# FLIGHT-CONTROLLER-Final_VERSION-1.net
KiCad netlist of a schematic drawn in EasyEDA Pro
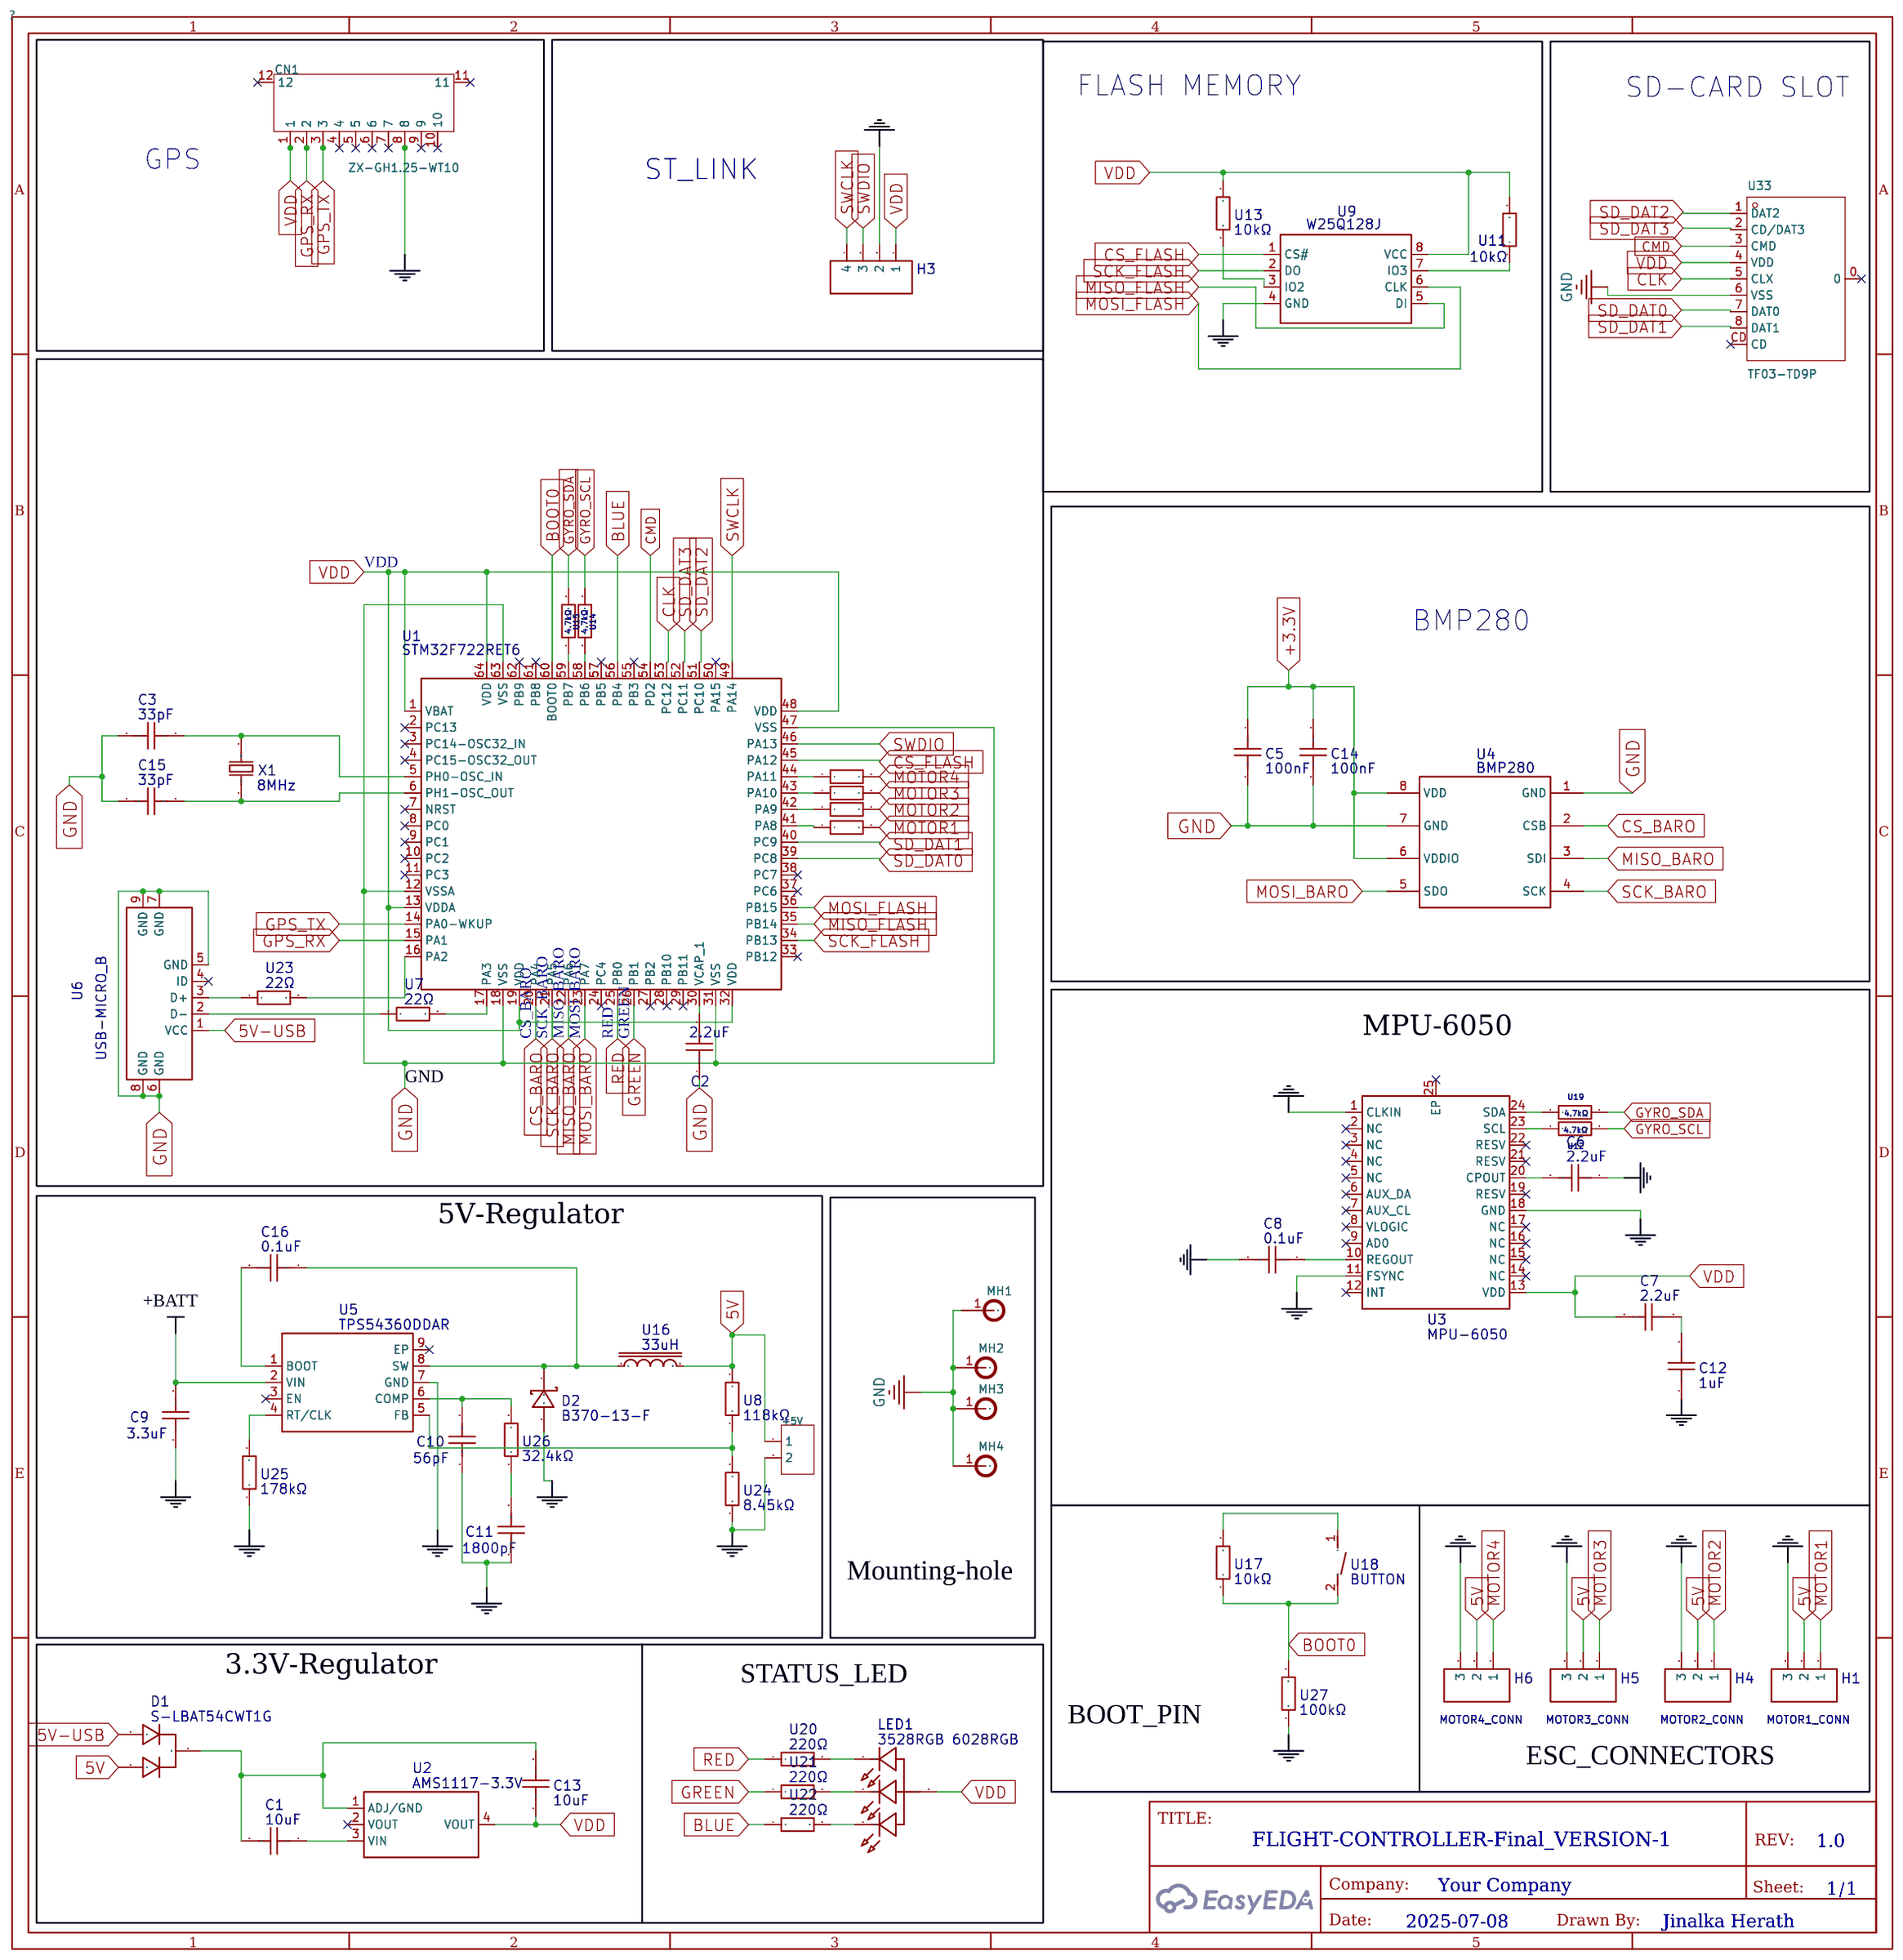
[diagram p0: schematic sheet]

(export (version "E")
  (design (tool "Eeschema 10.0.6"))
  (components
    (comp (ref "+5V")
      (value "~")
      (footprint "easyedapro:HDR-TH_2P-P2.54-V-F")
      (libsource (lib "easyedapro") (part "Header-Female-2.54_1x2"))
    )
    (comp (ref "C1")
      (value "10uF")
      (footprint "easyedapro:C0603")
      (fields
        (field (name "Manufacturer Part") "C1608CH2A560J080AA")
        (field (name "Manufacturer") "TDK")
        (field (name "Contributor") "lcsc")
      )
      (libsource (lib "easyedapro") (part "10uF"))
    )
    (comp (ref "C2")
      (value "2.2uF")
      (footprint "easyedapro:CAP-SMD_L3.2-W2.5-1")
      (fields
        (field (name "Manufacturer Part") "25MU225MB23225")
        (field (name "Manufacturer") "rubycon(红宝石)")
        (field (name "Contributor") "lcsc")
      )
      (libsource (lib "easyedapro") (part "2.2uF"))
    )
    (comp (ref "C3")
      (value "33pF")
      (footprint "easyedapro:C0603")
      (fields
        (field (name "Manufacturer Part") "C1608CH2A560J080AA")
        (field (name "Manufacturer") "TDK")
        (field (name "Contributor") "lcsc")
      )
      (libsource (lib "easyedapro") (part "33pF"))
    )
    (comp (ref "C5")
      (value "100nF")
      (footprint "easyedapro:C0603")
      (fields
        (field (name "Manufacturer Part") "C1608CH2A560J080AA")
        (field (name "Manufacturer") "TDK")
        (field (name "Contributor") "lcsc")
      )
      (libsource (lib "easyedapro") (part "100nF"))
    )
    (comp (ref "C6")
      (value "2.2uF")
      (footprint "easyedapro:CAP-SMD_L3.2-W2.5-1")
      (fields
        (field (name "Manufacturer Part") "25MU225MB23225")
        (field (name "Manufacturer") "rubycon(红宝石)")
        (field (name "Contributor") "lcsc")
      )
      (libsource (lib "easyedapro") (part "2.2uF"))
    )
    (comp (ref "C7")
      (value "2.2uF")
      (footprint "easyedapro:CAP-SMD_L3.2-W2.5-1")
      (fields
        (field (name "Manufacturer Part") "25MU225MB23225")
        (field (name "Manufacturer") "rubycon(红宝石)")
        (field (name "Contributor") "lcsc")
      )
      (libsource (lib "easyedapro") (part "2.2uF"))
    )
    (comp (ref "C8")
      (value "0.1uF")
      (footprint "easyedapro:C0603")
      (fields
        (field (name "Manufacturer Part") "C1608CH2A560J080AA")
        (field (name "Manufacturer") "TDK")
        (field (name "Contributor") "lcsc")
      )
      (libsource (lib "easyedapro") (part "0.1uF"))
    )
    (comp (ref "C9")
      (value "3.3uF")
      (footprint "easyedapro:C0603")
      (fields
        (field (name "Manufacturer Part") "C1608CH2A560J080AA")
        (field (name "Manufacturer") "TDK")
        (field (name "Contributor") "lcsc")
      )
      (libsource (lib "easyedapro") (part "3.3uF"))
    )
    (comp (ref "C10")
      (value "56pF")
      (footprint "easyedapro:C0603")
      (fields
        (field (name "Manufacturer Part") "C1608CH2A560J080AA")
        (field (name "Manufacturer") "TDK")
        (field (name "Contributor") "lcsc")
      )
      (libsource (lib "easyedapro") (part "56pF"))
    )
    (comp (ref "C11")
      (value "1800pF")
      (footprint "easyedapro:C0603")
      (fields
        (field (name "Manufacturer Part") "C1608CH2A560J080AA")
        (field (name "Manufacturer") "TDK")
        (field (name "Contributor") "lcsc")
      )
      (libsource (lib "easyedapro") (part "1800pF"))
    )
    (comp (ref "C12")
      (value "1uF")
      (footprint "easyedapro:C0603")
      (fields
        (field (name "Manufacturer Part") "C1608CH2A560J080AA")
        (field (name "Manufacturer") "TDK")
        (field (name "Contributor") "lcsc")
      )
      (libsource (lib "easyedapro") (part "1uF"))
    )
    (comp (ref "C13")
      (value "10uF")
      (footprint "easyedapro:C0603")
      (fields
        (field (name "Manufacturer Part") "C1608CH2A560J080AA")
        (field (name "Manufacturer") "TDK")
        (field (name "Contributor") "lcsc")
      )
      (libsource (lib "easyedapro") (part "10uF"))
    )
    (comp (ref "C14")
      (value "100nF")
      (footprint "easyedapro:C0603")
      (fields
        (field (name "Manufacturer Part") "C1608CH2A560J080AA")
        (field (name "Manufacturer") "TDK")
        (field (name "Contributor") "lcsc")
      )
      (libsource (lib "easyedapro") (part "100nF"))
    )
    (comp (ref "C15")
      (value "33pF")
      (footprint "easyedapro:C0603")
      (fields
        (field (name "Manufacturer Part") "C1608CH2A560J080AA")
        (field (name "Manufacturer") "TDK")
        (field (name "Contributor") "lcsc")
      )
      (libsource (lib "easyedapro") (part "33pF"))
    )
    (comp (ref "C16")
      (value "0.1uF")
      (footprint "easyedapro:C0603")
      (fields
        (field (name "Manufacturer Part") "C1608CH2A560J080AA")
        (field (name "Manufacturer") "TDK")
        (field (name "Contributor") "lcsc")
      )
      (libsource (lib "easyedapro") (part "0.1uF"))
    )
    (comp (ref "CN1")
      (value "ZX-GH1.25-WT10")
      (footprint "easyedapro:CONN-SMD_ZX-GH1.25-WT10")
      (fields (field (name "Manufacturer") "Megastar(兆星)"))
      (libsource (lib "easyedapro") (part "ZX-GH1.25-WT10"))
    )
    (comp (ref "D1")
      (value "S-LBAT54CWT1G")
      (footprint "easyedapro:SC-70-3_L2.0-W1.3-P1.30-LS2.1-BR")
      (fields (field (name "Manufacturer") "LRC(乐山无线电)") (field (name "Contributor") "lcsc"))
      (libsource (lib "easyedapro") (part "S-LBAT54CWT1G"))
    )
    (comp (ref "D2")
      (value "B370-13-F")
      (footprint "easyedapro:SMC_L7.1-W6.2-LS8.1-RD")
      (fields (field (name "Manufacturer") "DIODES(美台)") (field (name "Contributor") "LCSC"))
      (libsource (lib "easyedapro") (part "B370-13-F"))
    )
    (comp (ref "H1")
      (value "MOTOR1_CONN")
      (footprint "easyedapro:HDR-F-2.54_1X3")
      (fields (field (name "Contributor") "LCEDA_Lib"))
      (libsource (lib "easyedapro") (part "MOTOR1_CONN"))
    )
    (comp (ref "H3")
      (value "ST_LINK")
      (footprint "easyedapro:HDR-F-2.54_1X4")
      (fields (field (name "Contributor") "LCEDA_Lib"))
      (libsource (lib "easyedapro") (part "ST_LINK"))
    )
    (comp (ref "H4")
      (value "MOTOR2_CONN")
      (footprint "easyedapro:HDR-F-2.54_1X3")
      (fields (field (name "Contributor") "LCEDA_Lib"))
      (libsource (lib "easyedapro") (part "MOTOR2_CONN"))
    )
    (comp (ref "H5")
      (value "MOTOR3_CONN")
      (footprint "easyedapro:HDR-F-2.54_1X3")
      (fields (field (name "Contributor") "LCEDA_Lib"))
      (libsource (lib "easyedapro") (part "MOTOR3_CONN"))
    )
    (comp (ref "H6")
      (value "MOTOR4_CONN")
      (footprint "easyedapro:HDR-F-2.54_1X3")
      (fields (field (name "Contributor") "LCEDA_Lib"))
      (libsource (lib "easyedapro") (part "MOTOR4_CONN"))
    )
    (comp (ref "LED1")
      (value "3528RGB 6028RGB")
      (footprint "easyedapro:LED-SMD_4P-L3.5-W2.8_3528RGB-6028RGB")
      (fields
        (field (name "Manufacturer Part") "3528反贴RGB 6028反贴RGB 缺口蓝色")
        (field (name "Contributor") "lcsc")
      )
      (libsource (lib "easyedapro") (part "3528RGB 6028RGB"))
    )
    (comp (ref "MH1")
      (value "~")
      (footprint "easyedapro:MH_7.5")
      (libsource (lib "easyedapro") (part "MH_7.5"))
    )
    (comp (ref "MH2")
      (value "~")
      (footprint "easyedapro:MH_7.5")
      (libsource (lib "easyedapro") (part "MH_7.5"))
    )
    (comp (ref "MH3")
      (value "~")
      (footprint "easyedapro:MH_7.5")
      (libsource (lib "easyedapro") (part "MH_7.5"))
    )
    (comp (ref "MH4")
      (value "~")
      (footprint "easyedapro:MH_7.5")
      (libsource (lib "easyedapro") (part "MH_7.5"))
    )
    (comp (ref "U1")
      (value "STM32F722RET6")
      (footprint "easyedapro:LQFP-64_L10.0-W10.0-P0.50-LS12.0-BL")
      (fields (field (name "Manufacturer") "ST(意法半导体)") (field (name "Contributor") "LCSC"))
      (libsource (lib "easyedapro") (part "STM32F722RET6"))
    )
    (comp (ref "U2")
      (value "AMS1117-3.3V")
      (footprint "easyedapro:SOT-223-4_L6.5-W3.5-P2.30-LS7.0-BR")
      (fields (field (name "Manufacturer") "WPMtek(维攀)") (field (name "Contributor") "LCSC"))
      (libsource (lib "easyedapro") (part "AMS1117-3.3V"))
    )
    (comp (ref "U3")
      (value "MPU-6050")
      (footprint "easyedapro:QFN-24_L4.0-W4.0-P0.50-BL-EP2.7")
      (fields (field (name "Manufacturer") "TDK InvenSense(应美盛)"))
      (libsource (lib "easyedapro") (part "MPU-6050_C24112"))
    )
    (comp (ref "U4")
      (value "BMP280")
      (footprint "easyedapro:LGA-8_L2.5-W2.0-P0.65_AMP6127")
      (fields (field (name "Manufacturer") "Bosch(博世)"))
      (libsource (lib "easyedapro") (part "BMP280"))
    )
    (comp (ref "U5")
      (value "TPS54360DDAR")
      (footprint "easyedapro:ESOP-8_L4.9-W3.9-P1.27-LS6.0-BL-EP")
      (fields
        (field (name "Manufacturer Part") "TPS54360DDAR(TOKMAS)")
        (field (name "Manufacturer") "Tokmas(托克马斯)")
        (field (name "Contributor") "lcsc")
      )
      (libsource (lib "easyedapro") (part "TPS54360DDAR(TOKMAS)"))
    )
    (comp (ref "U6")
      (value "USB-MICRO_B")
      (footprint "easyedapro:MICRO-USB-SMD_USB-MICRO_B")
      (fields (field (name "Contributor") "LCSC"))
      (libsource (lib "easyedapro") (part "USB-MICRO_B"))
    )
    (comp (ref "U7")
      (value "22Ω")
      (footprint "easyedapro:RES-TH_BD2.3-L3.7-P7.70-D0.9")
      (fields
        (field (name "Manufacturer Part") "MF1/8W-220Ω±1%-ST52")
        (field (name "Manufacturer") "VO(翔胜)")
        (field (name "Contributor") "lcsc")
      )
      (libsource (lib "easyedapro") (part "22Ω"))
    )
    (comp (ref "U8")
      (value "118kΩ")
      (footprint "easyedapro:RES-TH_BD2.3-L3.7-P7.70-D0.9")
      (fields
        (field (name "Manufacturer Part") "MF1/8W-220Ω±1%-ST52")
        (field (name "Manufacturer") "VO(翔胜)")
        (field (name "Contributor") "lcsc")
      )
      (libsource (lib "easyedapro") (part "118kΩ"))
    )
    (comp (ref "U9")
      (value "W25Q128J")
      (footprint "easyedapro:SOIC-8_L5.3-W5.3-P1.27-LS8.0-BL")
      (fields (field (name "Manufacturer Part") "W25Q128JVSIQ") (field (name "Manufacturer") "WINBOND(华邦)"))
      (libsource (lib "easyedapro") (part "W25Q128JVSIQTR"))
    )
    (comp (ref "U11")
      (value "10kΩ")
      (footprint "easyedapro:RES-TH_BD2.3-L3.7-P7.70-D0.9")
      (fields
        (field (name "Manufacturer Part") "MF1/8W-220Ω±1%-ST52")
        (field (name "Manufacturer") "VO(翔胜)")
        (field (name "Contributor") "lcsc")
      )
      (libsource (lib "easyedapro") (part "10kΩ"))
    )
    (comp (ref "U12")
      (value "4.7kΩ")
      (footprint "easyedapro:RES-TH_BD2.3-L3.7-P7.70-D0.9")
      (fields
        (field (name "Manufacturer Part") "MF1/8W-220Ω±1%-ST52")
        (field (name "Manufacturer") "VO(翔胜)")
        (field (name "Contributor") "lcsc")
      )
      (libsource (lib "easyedapro") (part "4.7kΩ"))
    )
    (comp (ref "U13")
      (value "10kΩ")
      (footprint "easyedapro:RES-TH_BD2.3-L3.7-P7.70-D0.9")
      (fields
        (field (name "Manufacturer Part") "MF1/8W-220Ω±1%-ST52")
        (field (name "Manufacturer") "VO(翔胜)")
        (field (name "Contributor") "lcsc")
      )
      (libsource (lib "easyedapro") (part "10kΩ"))
    )
    (comp (ref "U14")
      (value "4.7kΩ")
      (footprint "easyedapro:RES-TH_BD2.3-L3.7-P7.70-D0.9")
      (fields
        (field (name "Manufacturer Part") "MF1/8W-220Ω±1%-ST52")
        (field (name "Manufacturer") "VO(翔胜)")
        (field (name "Contributor") "lcsc")
      )
      (libsource (lib "") (part "4.7kΩ_1"))
    )
    (comp (ref "U15")
      (value "4.7kΩ")
      (footprint "easyedapro:RES-TH_BD2.3-L3.7-P7.70-D0.9")
      (fields
        (field (name "Manufacturer Part") "MF1/8W-220Ω±1%-ST52")
        (field (name "Manufacturer") "VO(翔胜)")
        (field (name "Contributor") "lcsc")
      )
      (libsource (lib "") (part "4.7kΩ_1"))
    )
    (comp (ref "U16")
      (value "33uH")
      (footprint "easyedapro:IND-SMD_L8.5-W8.0_SMS0850")
      (fields
        (field (name "Manufacturer Part") "SMS0850-330MT")
        (field (name "Manufacturer") "LanTu Micro(蓝图微电)")
        (field (name "Contributor") "lcsc")
      )
      (libsource (lib "easyedapro") (part "33uH"))
    )
    (comp (ref "U17")
      (value "10kΩ")
      (footprint "easyedapro:RES-TH_BD2.3-L3.7-P7.70-D0.9")
      (fields
        (field (name "Manufacturer Part") "MF1/8W-220Ω±1%-ST52")
        (field (name "Manufacturer") "VO(翔胜)")
        (field (name "Contributor") "lcsc")
      )
      (libsource (lib "easyedapro") (part "10kΩ"))
    )
    (comp (ref "U18")
      (value "BUTTON")
      (footprint "easyedapro:KEY-SMD_L6.0-W6.0-LS6.6")
      (fields (field (name "Contributor") "lcsc"))
      (libsource (lib "easyedapro") (part "BUTTON"))
    )
    (comp (ref "U19")
      (value "4.7kΩ")
      (footprint "easyedapro:RES-TH_BD2.3-L3.7-P7.70-D0.9")
      (fields
        (field (name "Manufacturer Part") "MF1/8W-220Ω±1%-ST52")
        (field (name "Manufacturer") "VO(翔胜)")
        (field (name "Contributor") "lcsc")
      )
      (libsource (lib "easyedapro") (part "4.7kΩ"))
    )
    (comp (ref "U20")
      (value "220Ω")
      (footprint "easyedapro:RES-TH_BD2.3-L3.7-P7.70-D0.9")
      (fields
        (field (name "Manufacturer Part") "MF1/8W-220Ω±1%-ST52")
        (field (name "Manufacturer") "VO(翔胜)")
        (field (name "Contributor") "lcsc")
      )
      (libsource (lib "easyedapro") (part "220Ω"))
    )
    (comp (ref "U21")
      (value "220Ω")
      (footprint "easyedapro:RES-TH_BD2.3-L3.7-P7.70-D0.9")
      (fields
        (field (name "Manufacturer Part") "MF1/8W-220Ω±1%-ST52")
        (field (name "Manufacturer") "VO(翔胜)")
        (field (name "Contributor") "lcsc")
      )
      (libsource (lib "easyedapro") (part "220Ω"))
    )
    (comp (ref "U22")
      (value "220Ω")
      (footprint "easyedapro:RES-TH_BD2.3-L3.7-P7.70-D0.9")
      (fields
        (field (name "Manufacturer Part") "MF1/8W-220Ω±1%-ST52")
        (field (name "Manufacturer") "VO(翔胜)")
        (field (name "Contributor") "lcsc")
      )
      (libsource (lib "easyedapro") (part "220Ω"))
    )
    (comp (ref "U23")
      (value "22Ω")
      (footprint "easyedapro:RES-TH_BD2.3-L3.7-P7.70-D0.9")
      (fields
        (field (name "Manufacturer Part") "MF1/8W-220Ω±1%-ST52")
        (field (name "Manufacturer") "VO(翔胜)")
        (field (name "Contributor") "lcsc")
      )
      (libsource (lib "easyedapro") (part "22Ω"))
    )
    (comp (ref "U24")
      (value "8.45kΩ")
      (footprint "easyedapro:RES-TH_BD2.3-L3.7-P7.70-D0.9")
      (fields
        (field (name "Manufacturer Part") "MF1/8W-220Ω±1%-ST52")
        (field (name "Manufacturer") "VO(翔胜)")
        (field (name "Contributor") "lcsc")
      )
      (libsource (lib "easyedapro") (part "8.45kΩ"))
    )
    (comp (ref "U25")
      (value "178kΩ")
      (footprint "easyedapro:RES-TH_BD2.3-L3.7-P7.70-D0.9")
      (fields
        (field (name "Manufacturer Part") "MF1/8W-220Ω±1%-ST52")
        (field (name "Manufacturer") "VO(翔胜)")
        (field (name "Contributor") "lcsc")
      )
      (libsource (lib "easyedapro") (part "178kΩ"))
    )
    (comp (ref "U26")
      (value "32.4kΩ")
      (footprint "easyedapro:RES-TH_BD2.3-L3.7-P7.70-D0.9")
      (fields
        (field (name "Manufacturer Part") "MF1/8W-220Ω±1%-ST52")
        (field (name "Manufacturer") "VO(翔胜)")
        (field (name "Contributor") "lcsc")
      )
      (libsource (lib "easyedapro") (part "32.4kΩ"))
    )
    (comp (ref "U27")
      (value "100kΩ")
      (footprint "easyedapro:RES-TH_BD2.3-L3.7-P7.70-D0.9")
      (fields
        (field (name "Manufacturer Part") "MF1/8W-220Ω±1%-ST52")
        (field (name "Manufacturer") "VO(翔胜)")
        (field (name "Contributor") "lcsc")
      )
      (libsource (lib "easyedapro") (part "100kΩ"))
    )
    (comp (ref "U28")
      (value "100Ω")
      (footprint "easyedapro:RES-TH_BD2.3-L3.7-P7.70-D0.9")
      (fields
        (field (name "Manufacturer Part") "MF1/8W-220Ω±1%-ST52")
        (field (name "Manufacturer") "VO(翔胜)")
        (field (name "Contributor") "lcsc")
      )
      (libsource (lib "easyedapro") (part "100Ω"))
    )
    (comp (ref "U29")
      (value "100Ω")
      (footprint "easyedapro:RES-TH_BD2.3-L3.7-P7.70-D0.9")
      (fields
        (field (name "Manufacturer Part") "MF1/8W-220Ω±1%-ST52")
        (field (name "Manufacturer") "VO(翔胜)")
        (field (name "Contributor") "lcsc")
      )
      (libsource (lib "easyedapro") (part "100Ω"))
    )
    (comp (ref "U30")
      (value "100Ω")
      (footprint "easyedapro:RES-TH_BD2.3-L3.7-P7.70-D0.9")
      (fields
        (field (name "Manufacturer Part") "MF1/8W-220Ω±1%-ST52")
        (field (name "Manufacturer") "VO(翔胜)")
        (field (name "Contributor") "lcsc")
      )
      (libsource (lib "easyedapro") (part "100Ω"))
    )
    (comp (ref "U33")
      (value "TF03-TD9P")
      (footprint "easyedapro:CONN-SMD_TF-001A-P")
      (fields (field (name "Manufacturer") "BXCONN(宝讯)"))
      (libsource (lib "easyedapro") (part "TF03-TD9P"))
    )
    (comp (ref "U34")
      (value "100Ω")
      (footprint "easyedapro:RES-TH_BD2.3-L3.7-P7.70-D0.9")
      (fields
        (field (name "Manufacturer Part") "MF1/8W-220Ω±1%-ST52")
        (field (name "Manufacturer") "VO(翔胜)")
        (field (name "Contributor") "lcsc")
      )
      (libsource (lib "easyedapro") (part "100Ω"))
    )
    (comp (ref "X1")
      (value "8MHz")
      (footprint "easyedapro:CRYSTAL-SMD_L3.2-W2.5_3225-8MHZ")
      (fields
        (field (name "Manufacturer Part") "X22EL89COI-111YLC-8M")
        (field (name "Manufacturer") "YXC(扬兴晶振)")
        (field (name "Contributor") "lcsc")
      )
      (libsource (lib "easyedapro") (part "8MHz"))
    )
  )
  (nets
    (net (code "1") (name "+3.3V") (class "Default")
      (node (ref "C14") (pin "1") (pinfunction "1_1") (pintype "unspecified"))
      (node (ref "C5") (pin "1") (pinfunction "1_1") (pintype "unspecified"))
      (node (ref "U4") (pin "6") (pinfunction "VDDIO_6") (pintype "unspecified"))
      (node (ref "U4") (pin "8") (pinfunction "VDD_8") (pintype "unspecified"))
    )
    (net (code "2") (name "+BATT") (class "Default")
      (node (ref "C9") (pin "2") (pinfunction "2_2") (pintype "unspecified"))
      (node (ref "U5") (pin "2") (pinfunction "VIN_2") (pintype "unspecified"))
    )
    (net (code "3") (name "5V") (class "Default")
      (node (ref "+5V") (pin "1") (pinfunction "1_1") (pintype "input"))
      (node (ref "D1") (pin "2") (pinfunction "2_2") (pintype "unspecified"))
      (node (ref "H1") (pin "2") (pinfunction "2_2") (pintype "input"))
      (node (ref "H4") (pin "2") (pinfunction "2_2") (pintype "input"))
      (node (ref "H5") (pin "2") (pinfunction "2_2") (pintype "input"))
      (node (ref "H6") (pin "2") (pinfunction "2_2") (pintype "input"))
      (node (ref "U16") (pin "2") (pinfunction "2_2") (pintype "unspecified"))
      (node (ref "U8") (pin "2") (pinfunction "2_2") (pintype "unspecified"))
    )
    (net (code "4") (name "5V-USB") (class "Default")
      (node (ref "D1") (pin "1") (pinfunction "1_1") (pintype "unspecified"))
      (node (ref "U6") (pin "1") (pinfunction "VCC_1") (pintype "unspecified"))
    )
    (net (code "5") (name "BLUE") (class "Default")
      (node (ref "U1") (pin "56") (pinfunction "PB4_56") (pintype "unspecified"))
      (node (ref "U22") (pin "1") (pinfunction "1_1") (pintype "unspecified"))
    )
    (net (code "6") (name "BOOT0") (class "Default")
      (node (ref "U1") (pin "60") (pinfunction "BOOT0_60") (pintype "unspecified"))
      (node (ref "U17") (pin "1") (pinfunction "1_1") (pintype "unspecified"))
      (node (ref "U18") (pin "2") (pinfunction "B_2") (pintype "unspecified"))
      (node (ref "U27") (pin "2") (pinfunction "2_2") (pintype "unspecified"))
    )
    (net (code "7") (name "CLK") (class "Default")
      (node (ref "U1") (pin "53") (pinfunction "PC12_53") (pintype "unspecified"))
      (node (ref "U33") (pin "5") (pinfunction "CLX_5") (pintype "unspecified"))
    )
    (net (code "8") (name "CMD") (class "Default")
      (node (ref "U1") (pin "54") (pinfunction "PD2_54") (pintype "unspecified"))
      (node (ref "U33") (pin "3") (pinfunction "CMD_3") (pintype "unspecified"))
    )
    (net (code "9") (name "CS_BARO") (class "Default")
      (node (ref "U1") (pin "20") (pinfunction "PA4_20") (pintype "unspecified"))
      (node (ref "U4") (pin "2") (pinfunction "CSB_2") (pintype "unspecified"))
    )
    (net (code "10") (name "CS_FLASH") (class "Default")
      (node (ref "U1") (pin "45") (pinfunction "PA12_45") (pintype "unspecified"))
      (node (ref "U9") (pin "1") (pinfunction "CS#_1") (pintype "unspecified"))
    )
    (net (code "11") (name "GND") (class "Default")
      (node (ref "+5V") (pin "2") (pinfunction "2_2") (pintype "input"))
      (node (ref "C10") (pin "1") (pinfunction "1_1") (pintype "unspecified"))
      (node (ref "C11") (pin "1") (pinfunction "1_1") (pintype "unspecified"))
      (node (ref "C12") (pin "2") (pinfunction "2_2") (pintype "unspecified"))
      (node (ref "C14") (pin "2") (pinfunction "2_2") (pintype "unspecified"))
      (node (ref "C15") (pin "1") (pinfunction "1_1") (pintype "unspecified"))
      (node (ref "C2") (pin "1") (pinfunction "1_1") (pintype "unspecified"))
      (node (ref "C3") (pin "1") (pinfunction "1_1") (pintype "unspecified"))
      (node (ref "C5") (pin "2") (pinfunction "2_2") (pintype "unspecified"))
      (node (ref "C6") (pin "1") (pinfunction "1_1") (pintype "unspecified"))
      (node (ref "C8") (pin "2") (pinfunction "2_2") (pintype "unspecified"))
      (node (ref "C9") (pin "1") (pinfunction "1_1") (pintype "unspecified"))
      (node (ref "CN1") (pin "8") (pinfunction "8_8") (pintype "unspecified"))
      (node (ref "D2") (pin "2") (pinfunction "A_2") (pintype "unspecified"))
      (node (ref "H1") (pin "3") (pinfunction "3_3") (pintype "input"))
      (node (ref "H3") (pin "2") (pinfunction "2_2") (pintype "unspecified"))
      (node (ref "H4") (pin "3") (pinfunction "3_3") (pintype "input"))
      (node (ref "H5") (pin "3") (pinfunction "3_3") (pintype "input"))
      (node (ref "H6") (pin "3") (pinfunction "3_3") (pintype "input"))
      (node (ref "MH1") (pin "1") (pinfunction "1_1") (pintype "input"))
      (node (ref "MH2") (pin "1") (pinfunction "1_1") (pintype "input"))
      (node (ref "MH3") (pin "1") (pinfunction "1_1") (pintype "input"))
      (node (ref "MH4") (pin "1") (pinfunction "1_1") (pintype "input"))
      (node (ref "U1") (pin "12") (pinfunction "VSSA_12") (pintype "unspecified"))
      (node (ref "U1") (pin "18") (pinfunction "VSS_18") (pintype "unspecified"))
      (node (ref "U1") (pin "31") (pinfunction "VSS_31") (pintype "unspecified"))
      (node (ref "U1") (pin "47") (pinfunction "VSS_47") (pintype "unspecified"))
      (node (ref "U1") (pin "63") (pinfunction "VSS_63") (pintype "unspecified"))
      (node (ref "U24") (pin "1") (pinfunction "1_1") (pintype "unspecified"))
      (node (ref "U25") (pin "1") (pinfunction "1_1") (pintype "unspecified"))
      (node (ref "U27") (pin "1") (pinfunction "1_1") (pintype "unspecified"))
      (node (ref "U3") (pin "1") (pinfunction "CLKIN_1") (pintype "unspecified"))
      (node (ref "U3") (pin "11") (pinfunction "FSYNC_11") (pintype "unspecified"))
      (node (ref "U3") (pin "18") (pinfunction "GND_18") (pintype "unspecified"))
      (node (ref "U33") (pin "6") (pinfunction "VSS_6") (pintype "unspecified"))
      (node (ref "U4") (pin "1") (pinfunction "GND_1") (pintype "unspecified"))
      (node (ref "U4") (pin "7") (pinfunction "GND_7") (pintype "unspecified"))
      (node (ref "U5") (pin "7") (pinfunction "GND_7") (pintype "unspecified"))
      (node (ref "U6") (pin "5") (pinfunction "GND_5") (pintype "unspecified"))
      (node (ref "U6") (pin "6") (pinfunction "GND_6") (pintype "unspecified"))
      (node (ref "U6") (pin "7") (pinfunction "GND_7") (pintype "unspecified"))
      (node (ref "U6") (pin "8") (pinfunction "GND_8") (pintype "unspecified"))
      (node (ref "U6") (pin "9") (pinfunction "GND_9") (pintype "unspecified"))
      (node (ref "U9") (pin "4") (pinfunction "GND_4") (pintype "unspecified"))
    )
    (net (code "12") (name "GPS_RX") (class "Default")
      (node (ref "CN1") (pin "2") (pinfunction "2_2") (pintype "unspecified"))
      (node (ref "U1") (pin "15") (pinfunction "PA1_15") (pintype "unspecified"))
    )
    (net (code "13") (name "GPS_TX") (class "Default")
      (node (ref "CN1") (pin "3") (pinfunction "3_3") (pintype "unspecified"))
      (node (ref "U1") (pin "14") (pinfunction "PA0-WKUP_14") (pintype "unspecified"))
    )
    (net (code "14") (name "GREEN") (class "Default")
      (node (ref "U1") (pin "26") (pinfunction "PB1_26") (pintype "unspecified"))
      (node (ref "U21") (pin "1") (pinfunction "1_1") (pintype "unspecified"))
    )
    (net (code "15") (name "GYRO_SCL") (class "Default")
      (node (ref "U12") (pin "2") (pinfunction "2_2") (pintype "unspecified"))
      (node (ref "U14") (pin "2") (pinfunction "2_2") (pintype "unspecified"))
    )
    (net (code "16") (name "GYRO_SDA") (class "Default")
      (node (ref "U15") (pin "2") (pinfunction "2_2") (pintype "unspecified"))
      (node (ref "U19") (pin "2") (pinfunction "2_2") (pintype "unspecified"))
    )
    (net (code "17") (name "MISO_BARO") (class "Default")
      (node (ref "U1") (pin "22") (pinfunction "PA6_22") (pintype "unspecified"))
      (node (ref "U4") (pin "3") (pinfunction "SDI_3") (pintype "unspecified"))
    )
    (net (code "18") (name "MISO_FLASH") (class "Default")
      (node (ref "U1") (pin "35") (pinfunction "PB14_35") (pintype "unspecified"))
      (node (ref "U9") (pin "5") (pinfunction "DI_5") (pintype "unspecified"))
    )
    (net (code "19") (name "MOSI_BARO") (class "Default")
      (node (ref "U1") (pin "23") (pinfunction "PA7_23") (pintype "unspecified"))
      (node (ref "U4") (pin "5") (pinfunction "SDO_5") (pintype "unspecified"))
    )
    (net (code "20") (name "MOSI_FLASH") (class "Default")
      (node (ref "U1") (pin "36") (pinfunction "PB15_36") (pintype "unspecified"))
      (node (ref "U9") (pin "6") (pinfunction "CLK_6") (pintype "unspecified"))
    )
    (net (code "21") (name "MOTOR1") (class "Default")
      (node (ref "H1") (pin "1") (pinfunction "1_1") (pintype "input"))
      (node (ref "U34") (pin "2") (pinfunction "2_2") (pintype "unspecified"))
    )
    (net (code "22") (name "MOTOR2") (class "Default")
      (node (ref "H4") (pin "1") (pinfunction "1_1") (pintype "input"))
      (node (ref "U29") (pin "2") (pinfunction "2_2") (pintype "unspecified"))
    )
    (net (code "23") (name "MOTOR3") (class "Default")
      (node (ref "H5") (pin "1") (pinfunction "1_1") (pintype "input"))
      (node (ref "U28") (pin "2") (pinfunction "2_2") (pintype "unspecified"))
    )
    (net (code "24") (name "MOTOR4") (class "Default")
      (node (ref "H6") (pin "1") (pinfunction "1_1") (pintype "input"))
      (node (ref "U30") (pin "2") (pinfunction "2_2") (pintype "unspecified"))
    )
    (net (code "25") (name "Net-(C11-Pad2)") (class "Default")
      (node (ref "C11") (pin "2") (pinfunction "2_2") (pintype "unspecified"))
      (node (ref "U26") (pin "1") (pinfunction "1_1") (pintype "unspecified"))
    )
    (net (code "26") (name "Net-(C12-Pad1)") (class "Default")
      (node (ref "C12") (pin "1") (pinfunction "1_1") (pintype "unspecified"))
      (node (ref "C7") (pin "1") (pinfunction "1_1") (pintype "unspecified"))
    )
    (net (code "27") (name "Net-(D2-C)") (class "Default")
      (node (ref "C16") (pin "1") (pinfunction "1_1") (pintype "unspecified"))
      (node (ref "D2") (pin "1") (pinfunction "C_1") (pintype "unspecified"))
      (node (ref "U16") (pin "1") (pinfunction "1_1") (pintype "unspecified"))
      (node (ref "U5") (pin "8") (pinfunction "SW_8") (pintype "unspecified"))
    )
    (net (code "28") (name "Net-(LED1-B)") (class "Default")
      (node (ref "LED1") (pin "1") (pinfunction "B_1") (pintype "unspecified"))
      (node (ref "U21") (pin "2") (pinfunction "2_2") (pintype "unspecified"))
    )
    (net (code "29") (name "Net-(LED1-G)") (class "Default")
      (node (ref "LED1") (pin "4") (pinfunction "G_4") (pintype "unspecified"))
      (node (ref "U22") (pin "2") (pinfunction "2_2") (pintype "unspecified"))
    )
    (net (code "30") (name "Net-(LED1-R)") (class "Default")
      (node (ref "LED1") (pin "2") (pinfunction "R_2") (pintype "unspecified"))
      (node (ref "U20") (pin "2") (pinfunction "2_2") (pintype "unspecified"))
    )
    (net (code "31") (name "Net-(U1-PA2)") (class "Default")
      (node (ref "U1") (pin "16") (pinfunction "PA2_16") (pintype "unspecified"))
      (node (ref "U23") (pin "2") (pinfunction "2_2") (pintype "unspecified"))
    )
    (net (code "32") (name "Net-(U1-PA3)") (class "Default")
      (node (ref "U1") (pin "17") (pinfunction "PA3_17") (pintype "unspecified"))
      (node (ref "U7") (pin "2") (pinfunction "2_2") (pintype "unspecified"))
    )
    (net (code "33") (name "Net-(U1-PA8)") (class "Default")
      (node (ref "U1") (pin "41") (pinfunction "PA8_41") (pintype "unspecified"))
      (node (ref "U34") (pin "1") (pinfunction "1_1") (pintype "unspecified"))
    )
    (net (code "34") (name "Net-(U1-PA9)") (class "Default")
      (node (ref "U1") (pin "42") (pinfunction "PA9_42") (pintype "unspecified"))
      (node (ref "U29") (pin "1") (pinfunction "1_1") (pintype "unspecified"))
    )
    (net (code "35") (name "Net-(U1-PA10)") (class "Default")
      (node (ref "U1") (pin "43") (pinfunction "PA10_43") (pintype "unspecified"))
      (node (ref "U28") (pin "1") (pinfunction "1_1") (pintype "unspecified"))
    )
    (net (code "36") (name "Net-(U1-PA11)") (class "Default")
      (node (ref "U1") (pin "44") (pinfunction "PA11_44") (pintype "unspecified"))
      (node (ref "U30") (pin "1") (pinfunction "1_1") (pintype "unspecified"))
    )
    (net (code "37") (name "Net-(U1-PB6)") (class "Default")
      (node (ref "U1") (pin "58") (pinfunction "PB6_58") (pintype "unspecified"))
      (node (ref "U14") (pin "1") (pinfunction "1_1") (pintype "unspecified"))
    )
    (net (code "38") (name "Net-(U1-PB7)") (class "Default")
      (node (ref "U1") (pin "59") (pinfunction "PB7_59") (pintype "unspecified"))
      (node (ref "U15") (pin "1") (pinfunction "1_1") (pintype "unspecified"))
    )
    (net (code "39") (name "Net-(U1-PH0-OSC_IN)") (class "Default")
      (node (ref "C3") (pin "2") (pinfunction "2_2") (pintype "unspecified"))
      (node (ref "U1") (pin "5") (pinfunction "PH0-OSC_IN_5") (pintype "unspecified"))
      (node (ref "X1") (pin "2") (pinfunction "2_2") (pintype "unspecified"))
    )
    (net (code "40") (name "Net-(U1-PH1-OSC_OUT)") (class "Default")
      (node (ref "C15") (pin "2") (pinfunction "2_2") (pintype "unspecified"))
      (node (ref "U1") (pin "6") (pinfunction "PH1-OSC_OUT_6") (pintype "unspecified"))
      (node (ref "X1") (pin "1") (pinfunction "1_1") (pintype "unspecified"))
    )
    (net (code "41") (name "Net-(U1-VCAP_1)") (class "Default")
      (node (ref "C2") (pin "2") (pinfunction "2_2") (pintype "unspecified"))
      (node (ref "U1") (pin "30") (pinfunction "VCAP_1_30") (pintype "unspecified"))
    )
    (net (code "42") (name "Net-(U2-ADJ{slash}GND)") (class "Default")
      (node (ref "C1") (pin "2") (pinfunction "2_2") (pintype "unspecified"))
      (node (ref "C13") (pin "1") (pinfunction "1_1") (pintype "unspecified"))
      (node (ref "D1") (pin "3") (pinfunction "3_3") (pintype "unspecified"))
      (node (ref "U2") (pin "1") (pinfunction "ADJ/GND_1") (pintype "unspecified"))
    )
    (net (code "43") (name "Net-(U2-VIN)") (class "Default")
      (node (ref "C1") (pin "1") (pinfunction "1_1") (pintype "unspecified"))
      (node (ref "U2") (pin "3") (pinfunction "VIN_3") (pintype "unspecified"))
    )
    (net (code "44") (name "Net-(U3-CPOUT)") (class "Default")
      (node (ref "C6") (pin "2") (pinfunction "2_2") (pintype "unspecified"))
      (node (ref "U3") (pin "20") (pinfunction "CPOUT_20") (pintype "unspecified"))
    )
    (net (code "45") (name "Net-(U3-REGOUT)") (class "Default")
      (node (ref "C8") (pin "1") (pinfunction "1_1") (pintype "unspecified"))
      (node (ref "U3") (pin "10") (pinfunction "REGOUT_10") (pintype "unspecified"))
    )
    (net (code "46") (name "Net-(U3-SCL)") (class "Default")
      (node (ref "U12") (pin "1") (pinfunction "1_1") (pintype "unspecified"))
      (node (ref "U3") (pin "23") (pinfunction "SCL_23") (pintype "unspecified"))
    )
    (net (code "47") (name "Net-(U3-SDA)") (class "Default")
      (node (ref "U19") (pin "1") (pinfunction "1_1") (pintype "unspecified"))
      (node (ref "U3") (pin "24") (pinfunction "SDA_24") (pintype "unspecified"))
    )
    (net (code "48") (name "Net-(U5-BOOT)") (class "Default")
      (node (ref "C16") (pin "2") (pinfunction "2_2") (pintype "unspecified"))
      (node (ref "U5") (pin "1") (pinfunction "BOOT_1") (pintype "unspecified"))
    )
    (net (code "49") (name "Net-(U5-COMP)") (class "Default")
      (node (ref "C10") (pin "2") (pinfunction "2_2") (pintype "unspecified"))
      (node (ref "U26") (pin "2") (pinfunction "2_2") (pintype "unspecified"))
      (node (ref "U5") (pin "6") (pinfunction "COMP_6") (pintype "unspecified"))
    )
    (net (code "50") (name "Net-(U5-FB)") (class "Default")
      (node (ref "U24") (pin "2") (pinfunction "2_2") (pintype "unspecified"))
      (node (ref "U5") (pin "5") (pinfunction "FB_5") (pintype "unspecified"))
      (node (ref "U8") (pin "1") (pinfunction "1_1") (pintype "unspecified"))
    )
    (net (code "51") (name "Net-(U5-RT{slash}CLK)") (class "Default")
      (node (ref "U25") (pin "2") (pinfunction "2_2") (pintype "unspecified"))
      (node (ref "U5") (pin "4") (pinfunction "RT/CLK_4") (pintype "unspecified"))
    )
    (net (code "52") (name "Net-(U6-D+)") (class "Default")
      (node (ref "U23") (pin "1") (pinfunction "1_1") (pintype "unspecified"))
      (node (ref "U6") (pin "3") (pinfunction "D+_3") (pintype "unspecified"))
    )
    (net (code "53") (name "Net-(U6-D-)") (class "Default")
      (node (ref "U6") (pin "2") (pinfunction "D-_2") (pintype "unspecified"))
      (node (ref "U7") (pin "1") (pinfunction "1_1") (pintype "unspecified"))
    )
    (net (code "54") (name "Net-(U9-IO2)") (class "Default")
      (node (ref "U13") (pin "1") (pinfunction "1_1") (pintype "unspecified"))
      (node (ref "U9") (pin "3") (pinfunction "IO2_3") (pintype "unspecified"))
    )
    (net (code "55") (name "Net-(U9-IO3)") (class "Default")
      (node (ref "U11") (pin "1") (pinfunction "1_1") (pintype "unspecified"))
      (node (ref "U9") (pin "7") (pinfunction "IO3_7") (pintype "unspecified"))
    )
    (net (code "56") (name "Net-(U18-A)") (class "Default")
      (node (ref "U17") (pin "2") (pinfunction "2_2") (pintype "unspecified"))
      (node (ref "U18") (pin "1") (pinfunction "A_1") (pintype "unspecified"))
    )
    (net (code "57") (name "RED") (class "Default")
      (node (ref "U1") (pin "25") (pinfunction "PB0_25") (pintype "unspecified"))
      (node (ref "U20") (pin "1") (pinfunction "1_1") (pintype "unspecified"))
    )
    (net (code "58") (name "SCK_BARO") (class "Default")
      (node (ref "U1") (pin "21") (pinfunction "PA5_21") (pintype "unspecified"))
      (node (ref "U4") (pin "4") (pinfunction "SCK_4") (pintype "unspecified"))
    )
    (net (code "59") (name "SCK_FLASH") (class "Default")
      (node (ref "U1") (pin "34") (pinfunction "PB13_34") (pintype "unspecified"))
      (node (ref "U9") (pin "2") (pinfunction "DO_2") (pintype "unspecified"))
    )
    (net (code "60") (name "SD_DAT0") (class "Default")
      (node (ref "U1") (pin "39") (pinfunction "PC8_39") (pintype "unspecified"))
      (node (ref "U33") (pin "7") (pinfunction "DAT0_7") (pintype "unspecified"))
    )
    (net (code "61") (name "SD_DAT1") (class "Default")
      (node (ref "U1") (pin "40") (pinfunction "PC9_40") (pintype "unspecified"))
      (node (ref "U33") (pin "8") (pinfunction "DAT1_8") (pintype "unspecified"))
    )
    (net (code "62") (name "SD_DAT2") (class "Default")
      (node (ref "U1") (pin "51") (pinfunction "PC10_51") (pintype "unspecified"))
      (node (ref "U33") (pin "1") (pinfunction "DAT2_1") (pintype "unspecified"))
    )
    (net (code "63") (name "SD_DAT3") (class "Default")
      (node (ref "U1") (pin "52") (pinfunction "PC11_52") (pintype "unspecified"))
      (node (ref "U33") (pin "2") (pinfunction "CD/DAT3_2") (pintype "unspecified"))
    )
    (net (code "64") (name "SWCLK") (class "Default")
      (node (ref "H3") (pin "4") (pinfunction "4_4") (pintype "unspecified"))
      (node (ref "U1") (pin "49") (pinfunction "PA14_49") (pintype "unspecified"))
    )
    (net (code "65") (name "SWDIO") (class "Default")
      (node (ref "H3") (pin "3") (pinfunction "3_3") (pintype "unspecified"))
      (node (ref "U1") (pin "46") (pinfunction "PA13_46") (pintype "unspecified"))
    )
    (net (code "66") (name "VDD") (class "Default")
      (node (ref "C13") (pin "2") (pinfunction "2_2") (pintype "unspecified"))
      (node (ref "C7") (pin "2") (pinfunction "2_2") (pintype "unspecified"))
      (node (ref "CN1") (pin "1") (pinfunction "1_1") (pintype "unspecified"))
      (node (ref "H3") (pin "1") (pinfunction "1_1") (pintype "unspecified"))
      (node (ref "LED1") (pin "3") (pinfunction "A_3") (pintype "unspecified"))
      (node (ref "U1") (pin "1") (pinfunction "VBAT_1") (pintype "unspecified"))
      (node (ref "U1") (pin "13") (pinfunction "VDDA_13") (pintype "unspecified"))
      (node (ref "U1") (pin "19") (pinfunction "VDD_19") (pintype "unspecified"))
      (node (ref "U1") (pin "32") (pinfunction "VDD_32") (pintype "unspecified"))
      (node (ref "U1") (pin "48") (pinfunction "VDD_48") (pintype "unspecified"))
      (node (ref "U1") (pin "64") (pinfunction "VDD_64") (pintype "unspecified"))
      (node (ref "U11") (pin "2") (pinfunction "2_2") (pintype "unspecified"))
      (node (ref "U13") (pin "2") (pinfunction "2_2") (pintype "unspecified"))
      (node (ref "U2") (pin "4") (pinfunction "VOUT_4") (pintype "unspecified"))
      (node (ref "U3") (pin "13") (pinfunction "VDD_13") (pintype "unspecified"))
      (node (ref "U33") (pin "4") (pinfunction "VDD_4") (pintype "unspecified"))
      (node (ref "U9") (pin "8") (pinfunction "VCC_8") (pintype "unspecified"))
    )
    (net (code "67") (name "unconnected-(CN1-Pad4)") (class "Default")
      (node (ref "CN1") (pin "4") (pinfunction "4_4") (pintype "unspecified+no_connect"))
    )
    (net (code "68") (name "unconnected-(CN1-Pad5)") (class "Default")
      (node (ref "CN1") (pin "5") (pinfunction "5_5") (pintype "unspecified+no_connect"))
    )
    (net (code "69") (name "unconnected-(CN1-Pad6)") (class "Default")
      (node (ref "CN1") (pin "6") (pinfunction "6_6") (pintype "unspecified+no_connect"))
    )
    (net (code "70") (name "unconnected-(CN1-Pad7)") (class "Default")
      (node (ref "CN1") (pin "7") (pinfunction "7_7") (pintype "unspecified+no_connect"))
    )
    (net (code "71") (name "unconnected-(CN1-Pad9)") (class "Default")
      (node (ref "CN1") (pin "9") (pinfunction "9_9") (pintype "unspecified+no_connect"))
    )
    (net (code "72") (name "unconnected-(CN1-Pad10)") (class "Default")
      (node (ref "CN1") (pin "10") (pinfunction "10_10") (pintype "unspecified+no_connect"))
    )
    (net (code "73") (name "unconnected-(CN1-Pad11)") (class "Default")
      (node (ref "CN1") (pin "11") (pinfunction "11_11") (pintype "unspecified+no_connect"))
    )
    (net (code "74") (name "unconnected-(CN1-Pad12)") (class "Default")
      (node (ref "CN1") (pin "12") (pinfunction "12_12") (pintype "unspecified+no_connect"))
    )
    (net (code "75") (name "unconnected-(U1-NRST-Pad7)") (class "Default")
      (node (ref "U1") (pin "7") (pinfunction "NRST_7") (pintype "unspecified+no_connect"))
    )
    (net (code "76") (name "unconnected-(U1-PA15-Pad50)") (class "Default")
      (node (ref "U1") (pin "50") (pinfunction "PA15_50") (pintype "unspecified+no_connect"))
    )
    (net (code "77") (name "unconnected-(U1-PB2-Pad27)") (class "Default")
      (node (ref "U1") (pin "27") (pinfunction "PB2_27") (pintype "unspecified+no_connect"))
    )
    (net (code "78") (name "unconnected-(U1-PB3-Pad55)") (class "Default")
      (node (ref "U1") (pin "55") (pinfunction "PB3_55") (pintype "unspecified+no_connect"))
    )
    (net (code "79") (name "unconnected-(U1-PB5-Pad57)") (class "Default")
      (node (ref "U1") (pin "57") (pinfunction "PB5_57") (pintype "unspecified+no_connect"))
    )
    (net (code "80") (name "unconnected-(U1-PB8-Pad61)") (class "Default")
      (node (ref "U1") (pin "61") (pinfunction "PB8_61") (pintype "unspecified+no_connect"))
    )
    (net (code "81") (name "unconnected-(U1-PB9-Pad62)") (class "Default")
      (node (ref "U1") (pin "62") (pinfunction "PB9_62") (pintype "unspecified+no_connect"))
    )
    (net (code "82") (name "unconnected-(U1-PB10-Pad28)") (class "Default")
      (node (ref "U1") (pin "28") (pinfunction "PB10_28") (pintype "unspecified+no_connect"))
    )
    (net (code "83") (name "unconnected-(U1-PB11-Pad29)") (class "Default")
      (node (ref "U1") (pin "29") (pinfunction "PB11_29") (pintype "unspecified+no_connect"))
    )
    (net (code "84") (name "unconnected-(U1-PB12-Pad33)") (class "Default")
      (node (ref "U1") (pin "33") (pinfunction "PB12_33") (pintype "unspecified+no_connect"))
    )
    (net (code "85") (name "unconnected-(U1-PC0-Pad8)") (class "Default")
      (node (ref "U1") (pin "8") (pinfunction "PC0_8") (pintype "unspecified+no_connect"))
    )
    (net (code "86") (name "unconnected-(U1-PC1-Pad9)") (class "Default")
      (node (ref "U1") (pin "9") (pinfunction "PC1_9") (pintype "unspecified+no_connect"))
    )
    (net (code "87") (name "unconnected-(U1-PC2-Pad10)") (class "Default")
      (node (ref "U1") (pin "10") (pinfunction "PC2_10") (pintype "unspecified+no_connect"))
    )
    (net (code "88") (name "unconnected-(U1-PC3-Pad11)") (class "Default")
      (node (ref "U1") (pin "11") (pinfunction "PC3_11") (pintype "unspecified+no_connect"))
    )
    (net (code "89") (name "unconnected-(U1-PC4-Pad24)") (class "Default")
      (node (ref "U1") (pin "24") (pinfunction "PC4_24") (pintype "unspecified+no_connect"))
    )
    (net (code "90") (name "unconnected-(U1-PC6-Pad37)") (class "Default")
      (node (ref "U1") (pin "37") (pinfunction "PC6_37") (pintype "unspecified+no_connect"))
    )
    (net (code "91") (name "unconnected-(U1-PC7-Pad38)") (class "Default")
      (node (ref "U1") (pin "38") (pinfunction "PC7_38") (pintype "unspecified+no_connect"))
    )
    (net (code "92") (name "unconnected-(U1-PC13-Pad2)") (class "Default")
      (node (ref "U1") (pin "2") (pinfunction "PC13_2") (pintype "unspecified+no_connect"))
    )
    (net (code "93") (name "unconnected-(U1-PC14-OSC32_IN-Pad3)") (class "Default")
      (node (ref "U1") (pin "3") (pinfunction "PC14-OSC32_IN_3") (pintype "unspecified+no_connect"))
    )
    (net (code "94") (name "unconnected-(U1-PC15-OSC32_OUT-Pad4)") (class "Default")
      (node (ref "U1") (pin "4") (pinfunction "PC15-OSC32_OUT_4") (pintype "unspecified+no_connect"))
    )
    (net (code "95") (name "unconnected-(U2-VOUT-Pad2)") (class "Default")
      (node (ref "U2") (pin "2") (pinfunction "VOUT_2") (pintype "unspecified+no_connect"))
    )
    (net (code "96") (name "unconnected-(U3-AD0-Pad9)") (class "Default")
      (node (ref "U3") (pin "9") (pinfunction "AD0_9") (pintype "unspecified+no_connect"))
    )
    (net (code "97") (name "unconnected-(U3-AUX_CL-Pad7)") (class "Default")
      (node (ref "U3") (pin "7") (pinfunction "AUX_CL_7") (pintype "unspecified+no_connect"))
    )
    (net (code "98") (name "unconnected-(U3-AUX_DA-Pad6)") (class "Default")
      (node (ref "U3") (pin "6") (pinfunction "AUX_DA_6") (pintype "unspecified+no_connect"))
    )
    (net (code "99") (name "unconnected-(U3-EP-Pad25)") (class "Default")
      (node (ref "U3") (pin "25") (pinfunction "EP_25") (pintype "unspecified+no_connect"))
    )
    (net (code "100") (name "unconnected-(U3-INT-Pad12)") (class "Default")
      (node (ref "U3") (pin "12") (pinfunction "INT_12") (pintype "unspecified+no_connect"))
    )
    (net (code "101") (name "unconnected-(U3-NC-Pad2)") (class "Default")
      (node (ref "U3") (pin "2") (pinfunction "NC_2") (pintype "unspecified+no_connect"))
    )
    (net (code "102") (name "unconnected-(U3-NC-Pad3)") (class "Default")
      (node (ref "U3") (pin "3") (pinfunction "NC_3") (pintype "unspecified+no_connect"))
    )
    (net (code "103") (name "unconnected-(U3-NC-Pad4)") (class "Default")
      (node (ref "U3") (pin "4") (pinfunction "NC_4") (pintype "unspecified+no_connect"))
    )
    (net (code "104") (name "unconnected-(U3-NC-Pad5)") (class "Default")
      (node (ref "U3") (pin "5") (pinfunction "NC_5") (pintype "unspecified+no_connect"))
    )
    (net (code "105") (name "unconnected-(U3-NC-Pad14)") (class "Default")
      (node (ref "U3") (pin "14") (pinfunction "NC_14") (pintype "unspecified+no_connect"))
    )
    (net (code "106") (name "unconnected-(U3-NC-Pad15)") (class "Default")
      (node (ref "U3") (pin "15") (pinfunction "NC_15") (pintype "unspecified+no_connect"))
    )
    (net (code "107") (name "unconnected-(U3-NC-Pad16)") (class "Default")
      (node (ref "U3") (pin "16") (pinfunction "NC_16") (pintype "unspecified+no_connect"))
    )
    (net (code "108") (name "unconnected-(U3-NC-Pad17)") (class "Default")
      (node (ref "U3") (pin "17") (pinfunction "NC_17") (pintype "unspecified+no_connect"))
    )
    (net (code "109") (name "unconnected-(U3-RESV-Pad19)") (class "Default")
      (node (ref "U3") (pin "19") (pinfunction "RESV_19") (pintype "unspecified+no_connect"))
    )
    (net (code "110") (name "unconnected-(U3-RESV-Pad21)") (class "Default")
      (node (ref "U3") (pin "21") (pinfunction "RESV_21") (pintype "unspecified+no_connect"))
    )
    (net (code "111") (name "unconnected-(U3-RESV-Pad22)") (class "Default")
      (node (ref "U3") (pin "22") (pinfunction "RESV_22") (pintype "unspecified+no_connect"))
    )
    (net (code "112") (name "unconnected-(U3-VLOGIC-Pad8)") (class "Default")
      (node (ref "U3") (pin "8") (pinfunction "VLOGIC_8") (pintype "unspecified+no_connect"))
    )
    (net (code "113") (name "unconnected-(U5-EN-Pad3)") (class "Default")
      (node (ref "U5") (pin "3") (pinfunction "EN_3") (pintype "unspecified+no_connect"))
    )
    (net (code "114") (name "unconnected-(U5-EP-Pad9)") (class "Default")
      (node (ref "U5") (pin "9") (pinfunction "EP_9") (pintype "unspecified+no_connect"))
    )
    (net (code "115") (name "unconnected-(U6-ID-Pad4)") (class "Default")
      (node (ref "U6") (pin "4") (pinfunction "ID_4") (pintype "unspecified+no_connect"))
    )
    (net (code "116") (name "unconnected-(U33-Pad0)") (class "Default")
      (node (ref "U33") (pin "0") (pinfunction "0_0") (pintype "unspecified+no_connect"))
    )
    (net (code "117") (name "unconnected-(U33-PadCD)") (class "Default")
      (node (ref "U33") (pin "CD") (pinfunction "CD_CD") (pintype "unspecified+no_connect"))
    )
  )
)
